# sensor.net
KiCad netlist of a schematic drawn in EAGLE
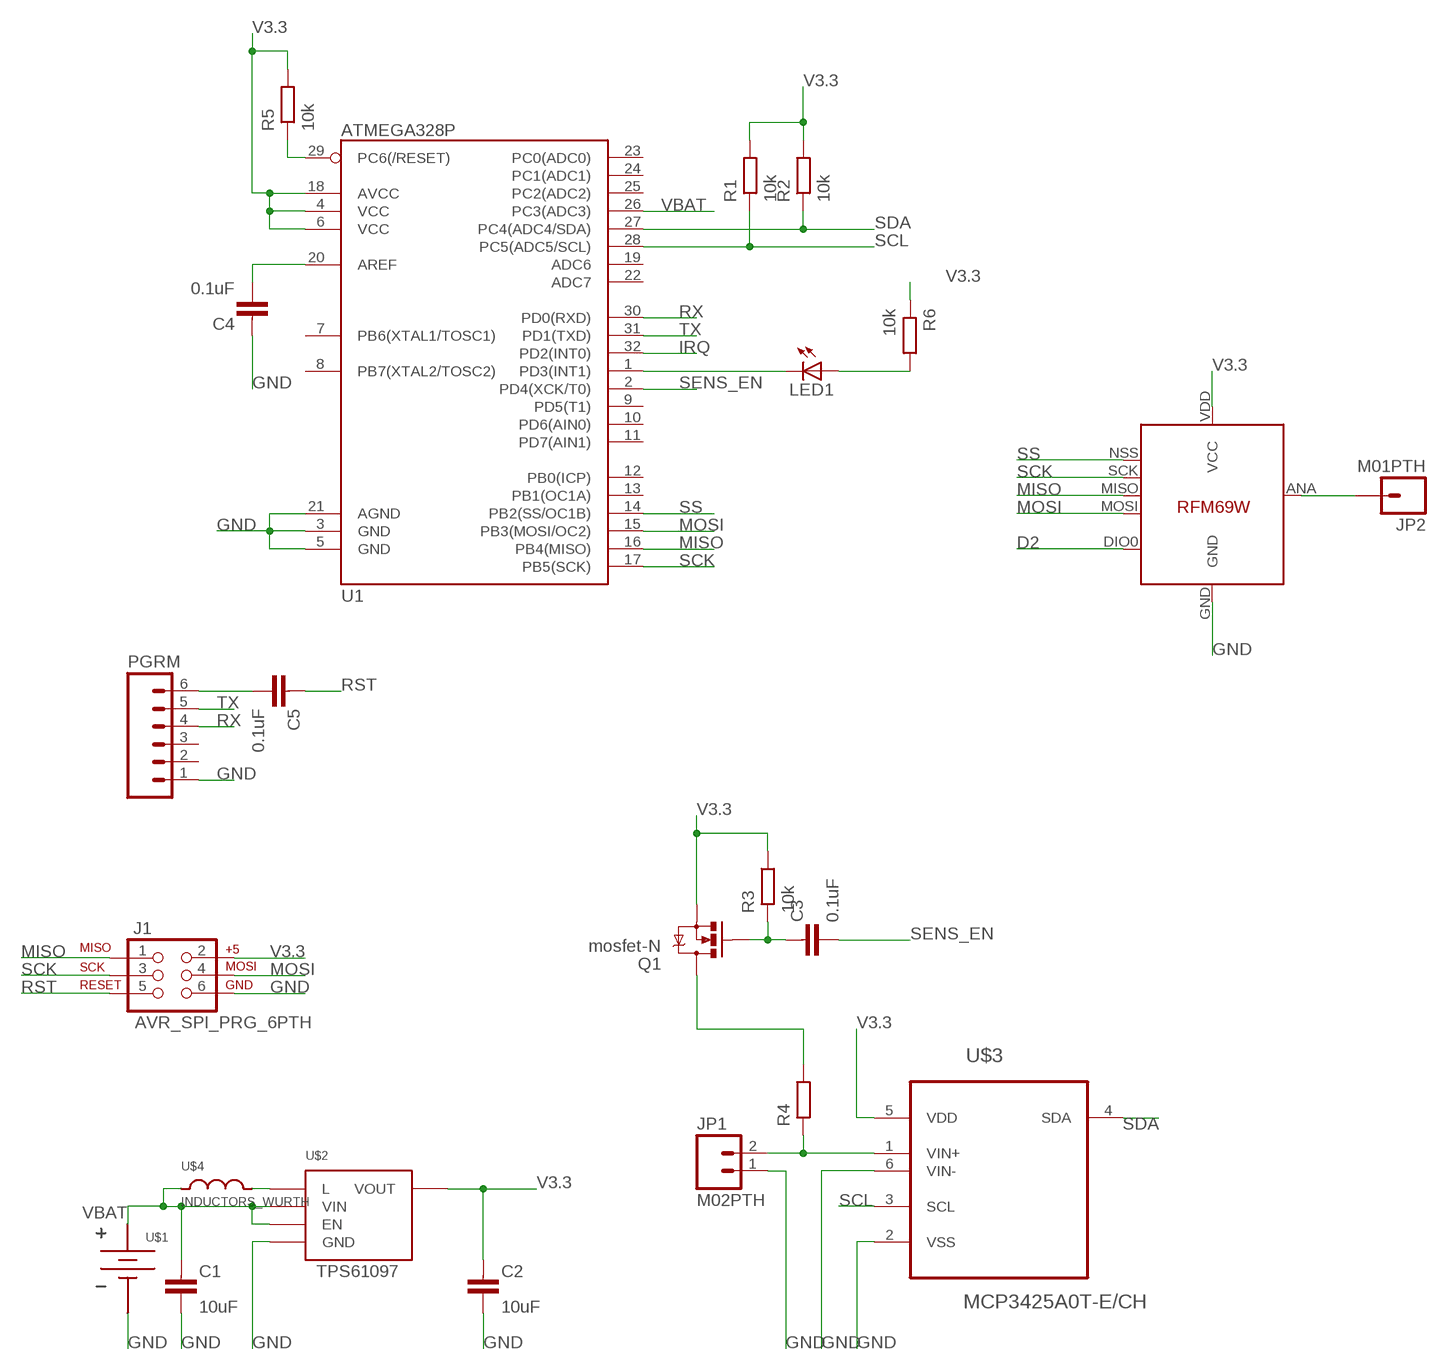
[diagram p0: schematic, sheet 1]

(export (version "E")
  (design (tool "Eeschema 10.0.6"))
  (components
    (comp (ref "C1")
      (value "10uF")
      (footprint "eagle-import:C0805-N")
      (libsource (lib "eagle-import") (part "CAPACITOR0805-N"))
    )
    (comp (ref "C2")
      (value "10uF")
      (footprint "eagle-import:C0805-N")
      (libsource (lib "eagle-import") (part "CAPACITOR0805-N"))
    )
    (comp (ref "C3")
      (value "0.1uF")
      (footprint "eagle-import:C0603-N")
      (libsource (lib "eagle-import") (part "CAPACITOR0603-N"))
    )
    (comp (ref "C4")
      (value "0.1uF")
      (footprint "eagle-import:C0603-N")
      (libsource (lib "eagle-import") (part "CAPACITOR0603-N"))
    )
    (comp (ref "C5")
      (value "0.1uF")
      (footprint "eagle-import:C0603-N")
      (libsource (lib "eagle-import") (part "CAPACITOR0603-N"))
    )
    (comp (ref "J1")
      (value "AVR_SPI_PRG_6PTH")
      (footprint "eagle-import:2X3")
      (libsource (lib "eagle-import") (part "AVR_SPI_PRG_6PTH"))
    )
    (comp (ref "JP1")
      (value "M02PTH")
      (footprint "eagle-import:1X02")
      (libsource (lib "eagle-import") (part "M02PTH"))
    )
    (comp (ref "JP2")
      (value "M01PTH")
      (footprint "eagle-import:1X01")
      (libsource (lib "eagle-import") (part "M01PTH"))
    )
    (comp (ref "LED1")
      (value "LED0603")
      (footprint "eagle-import:LED-0603")
      (libsource (lib "eagle-import") (part "LED0603"))
    )
    (comp (ref "PGRM")
      (value "M06LONGPADS")
      (footprint "eagle-import:1X06_LONGPADS")
      (libsource (lib "eagle-import") (part "M06LONGPADS"))
    )
    (comp (ref "Q1")
      (value "mosfet-N")
      (footprint "eagle-import:SOT23")
      (libsource (lib "eagle-import") (part "MOSFET-NCHANNELBSS123LT1G"))
    )
    (comp (ref "R1")
      (value "10k")
      (footprint "eagle-import:R0603-N")
      (libsource (lib "eagle-import") (part "RESISTOR0603-N"))
    )
    (comp (ref "R2")
      (value "10k")
      (footprint "eagle-import:R0603-N")
      (libsource (lib "eagle-import") (part "RESISTOR0603-N"))
    )
    (comp (ref "R3")
      (value "10k")
      (footprint "eagle-import:R0603-N")
      (libsource (lib "eagle-import") (part "RESISTOR0603-N"))
    )
    (comp (ref "R4")
      (value "RESISTOR0603-N")
      (footprint "eagle-import:R0603-N")
      (libsource (lib "eagle-import") (part "RESISTOR0603-N"))
    )
    (comp (ref "R5")
      (value "10k")
      (footprint "eagle-import:R0603-N")
      (libsource (lib "eagle-import") (part "RESISTOR0603-N"))
    )
    (comp (ref "R6")
      (value "10k")
      (footprint "eagle-import:R0603-N")
      (libsource (lib "eagle-import") (part "RESISTOR0603-N"))
    )
    (comp (ref "U$1")
      (value "KEYSTONEAAHOLDER_2CELL")
      (footprint "eagle-import:KEYSTONEAAHOLDER_2CELL")
      (libsource (lib "eagle-import") (part "KEYSTONEAAHOLDER_2CELL"))
    )
    (comp (ref "U$2")
      (value "TPS61097-33")
      (footprint "eagle-import:SOT23-5")
      (libsource (lib "eagle-import") (part "TPS61097-33"))
    )
    (comp (ref "U$3")
      (value "MCP3425A0T-E/CH")
      (footprint "eagle-import:SOT95P270X145-6N")
      (libsource (lib "eagle-import") (part "MCP3425A0T-E/CH"))
    )
    (comp (ref "U$4")
      (value "INDUCTORS_WURTH")
      (footprint "eagle-import:WURTH_10UH_650MA")
      (libsource (lib "eagle-import") (part "INDUCTORS_WURTH"))
    )
    (comp (ref "U$5")
      (value "RFM69")
      (footprint "eagle-import:RFM69W-MINPADS")
      (libsource (lib "eagle-import") (part "RFM69"))
    )
    (comp (ref "U1")
      (value "ATMEGA328P")
      (footprint "eagle-import:TQFP32-08")
      (libsource (lib "eagle-import") (part "ATMEGA328_SMT"))
    )
  )
  (nets
    (net (code "1") (name "/D2") (class "Default")
      (node (ref "U$5") (pin "DIO0") (pinfunction "DIO0_DIO0") (pintype "open_collector"))
    )
    (net (code "2") (name "/GND") (class "Default")
      (node (ref "C1") (pin "2") (pinfunction "2_2") (pintype "passive"))
      (node (ref "C2") (pin "2") (pinfunction "2_2") (pintype "passive"))
      (node (ref "C4") (pin "1") (pinfunction "1_1") (pintype "passive"))
      (node (ref "J1") (pin "6") (pinfunction "6_6") (pintype "passive"))
      (node (ref "JP1") (pin "1") (pinfunction "1_1") (pintype "passive"))
      (node (ref "PGRM") (pin "1") (pinfunction "1_1") (pintype "passive"))
      (node (ref "U$1") (pin "P$2") (pinfunction "GND_P$2") (pintype "bidirectional"))
      (node (ref "U$2") (pin "P$2") (pinfunction "GND_P$2") (pintype "power_in"))
      (node (ref "U$3") (pin "2") (pinfunction "VSS_2") (pintype "passive"))
      (node (ref "U$3") (pin "6") (pinfunction "VIN-_6") (pintype "input"))
      (node (ref "U$5") (pin "GND") (pinfunction "GND_GND") (pintype "power_in"))
      (node (ref "U1") (pin "21") (pinfunction "AGND_21") (pintype "bidirectional"))
      (node (ref "U1") (pin "3") (pinfunction "GND_3") (pintype "bidirectional"))
      (node (ref "U1") (pin "5") (pinfunction "GND_5") (pintype "bidirectional"))
    )
    (net (code "3") (name "/IRQ") (class "Default")
      (node (ref "U1") (pin "32") (pinfunction "PD2(INT0)_32") (pintype "bidirectional"))
    )
    (net (code "4") (name "/MISO") (class "Default")
      (node (ref "J1") (pin "1") (pinfunction "1_1") (pintype "passive"))
      (node (ref "U$5") (pin "MISO") (pinfunction "MISO_MISO") (pintype "input"))
      (node (ref "U1") (pin "16") (pinfunction "PB4(MISO)_16") (pintype "bidirectional"))
    )
    (net (code "5") (name "/MOSI") (class "Default")
      (node (ref "J1") (pin "4") (pinfunction "4_4") (pintype "passive"))
      (node (ref "U$5") (pin "MOSI") (pinfunction "MOSI_MOSI") (pintype "output"))
      (node (ref "U1") (pin "15") (pinfunction "PB3(MOSI/OC2)_15") (pintype "bidirectional"))
    )
    (net (code "6") (name "/RST") (class "Default")
      (node (ref "C5") (pin "1") (pinfunction "1_1") (pintype "passive"))
      (node (ref "J1") (pin "5") (pinfunction "5_5") (pintype "passive"))
      (node (ref "R5") (pin "1") (pinfunction "P$1_1") (pintype "passive"))
      (node (ref "U1") (pin "29") (pinfunction "PC6(/RESET)_29") (pintype "bidirectional"))
    )
    (net (code "7") (name "/RX") (class "Default")
      (node (ref "PGRM") (pin "4") (pinfunction "4_4") (pintype "passive"))
      (node (ref "U1") (pin "30") (pinfunction "PD0(RXD)_30") (pintype "bidirectional"))
    )
    (net (code "8") (name "/SCK") (class "Default")
      (node (ref "J1") (pin "3") (pinfunction "3_3") (pintype "passive"))
      (node (ref "U$5") (pin "SCK") (pinfunction "SCK_SCK") (pintype "input"))
      (node (ref "U1") (pin "17") (pinfunction "PB5(SCK)_17") (pintype "bidirectional"))
    )
    (net (code "9") (name "/SCL") (class "Default")
      (node (ref "R1") (pin "1") (pinfunction "P$1_1") (pintype "passive"))
      (node (ref "U$3") (pin "3") (pinfunction "SCL_3") (pintype "input"))
      (node (ref "U1") (pin "28") (pinfunction "PC5(ADC5/SCL)_28") (pintype "bidirectional"))
    )
    (net (code "10") (name "/SDA") (class "Default")
      (node (ref "R2") (pin "1") (pinfunction "P$1_1") (pintype "passive"))
      (node (ref "U$3") (pin "4") (pinfunction "SDA_4") (pintype "bidirectional"))
      (node (ref "U1") (pin "27") (pinfunction "PC4(ADC4/SDA)_27") (pintype "bidirectional"))
    )
    (net (code "11") (name "/SENS_EN") (class "Default")
      (node (ref "C3") (pin "2") (pinfunction "2_2") (pintype "passive"))
      (node (ref "U1") (pin "2") (pinfunction "PD4(XCK/T0)_2") (pintype "bidirectional"))
    )
    (net (code "12") (name "/SS") (class "Default")
      (node (ref "U$5") (pin "NSS") (pinfunction "SEL_NSS") (pintype "input"))
      (node (ref "U1") (pin "14") (pinfunction "PB2(SS/OC1B)_14") (pintype "bidirectional"))
    )
    (net (code "13") (name "/TX") (class "Default")
      (node (ref "PGRM") (pin "5") (pinfunction "5_5") (pintype "passive"))
      (node (ref "U1") (pin "31") (pinfunction "PD1(TXD)_31") (pintype "bidirectional"))
    )
    (net (code "14") (name "/V3.3") (class "Default")
      (node (ref "C2") (pin "1") (pinfunction "1_1") (pintype "passive"))
      (node (ref "J1") (pin "2") (pinfunction "2_2") (pintype "passive"))
      (node (ref "Q1") (pin "2") (pinfunction "S_2") (pintype "passive"))
      (node (ref "R1") (pin "2") (pinfunction "P$2_2") (pintype "passive"))
      (node (ref "R2") (pin "2") (pinfunction "P$2_2") (pintype "passive"))
      (node (ref "R3") (pin "2") (pinfunction "P$2_2") (pintype "passive"))
      (node (ref "R5") (pin "2") (pinfunction "P$2_2") (pintype "passive"))
      (node (ref "R6") (pin "1") (pinfunction "P$1_1") (pintype "passive"))
      (node (ref "U$2") (pin "P$4") (pinfunction "VOUT_P$4") (pintype "power_in"))
      (node (ref "U$3") (pin "5") (pinfunction "VDD_5") (pintype "power_in"))
      (node (ref "U$5") (pin "VDD") (pinfunction "VCC_VDD") (pintype "power_in"))
      (node (ref "U1") (pin "18") (pinfunction "AVCC_18") (pintype "bidirectional"))
      (node (ref "U1") (pin "4") (pinfunction "VCC_4") (pintype "bidirectional"))
      (node (ref "U1") (pin "6") (pinfunction "VCC_6") (pintype "bidirectional"))
    )
    (net (code "15") (name "/VBAT") (class "Default")
      (node (ref "C1") (pin "1") (pinfunction "1_1") (pintype "passive"))
      (node (ref "U$1") (pin "P$1") (pinfunction "VBAT_P$1") (pintype "bidirectional"))
      (node (ref "U$2") (pin "P$1") (pinfunction "VIN_P$1") (pintype "power_in"))
      (node (ref "U$2") (pin "P$3") (pinfunction "EN_P$3") (pintype "bidirectional"))
      (node (ref "U$4") (pin "P$2") (pinfunction "P$2_P$2") (pintype "passive"))
      (node (ref "U1") (pin "26") (pinfunction "PC3(ADC3)_26") (pintype "bidirectional"))
    )
    (net (code "16") (name "Net-(C5-Pad2)") (class "Default")
      (node (ref "C5") (pin "2") (pinfunction "2_2") (pintype "passive"))
      (node (ref "PGRM") (pin "6") (pinfunction "6_6") (pintype "passive"))
    )
    (net (code "17") (name "Net-(Q1-D)") (class "Default")
      (node (ref "Q1") (pin "3") (pinfunction "D_3") (pintype "passive"))
      (node (ref "R4") (pin "2") (pinfunction "P$2_2") (pintype "passive"))
    )
    (net (code "18") (name "Net-(Q1-G)") (class "Default")
      (node (ref "C3") (pin "1") (pinfunction "1_1") (pintype "passive"))
      (node (ref "Q1") (pin "1") (pinfunction "G_1") (pintype "passive"))
      (node (ref "R3") (pin "1") (pinfunction "P$1_1") (pintype "passive"))
    )
    (net (code "19") (name "Net-(R4-P$1)") (class "Default")
      (node (ref "JP1") (pin "2") (pinfunction "2_2") (pintype "passive"))
      (node (ref "R4") (pin "1") (pinfunction "P$1_1") (pintype "passive"))
      (node (ref "U$3") (pin "1") (pinfunction "VIN+_1") (pintype "input"))
    )
    (net (code "20") (name "Net-(R6-P$2)") (class "Default")
      (node (ref "LED1") (pin "A") (pinfunction "A_A") (pintype "passive"))
      (node (ref "R6") (pin "2") (pinfunction "P$2_2") (pintype "passive"))
    )
    (net (code "21") (name "Net-(U$2-L)") (class "Default")
      (node (ref "U$2") (pin "P$5") (pinfunction "L_P$5") (pintype "bidirectional"))
      (node (ref "U$4") (pin "P$1") (pinfunction "P$1_P$1") (pintype "passive"))
    )
    (net (code "22") (name "Net-(U$5-ANT)") (class "Default")
      (node (ref "JP2") (pin "1") (pinfunction "1_1") (pintype "passive"))
      (node (ref "U$5") (pin "ANA") (pinfunction "ANT_ANA") (pintype "passive"))
    )
    (net (code "23") (name "Net-(U1-AREF)") (class "Default")
      (node (ref "C4") (pin "2") (pinfunction "2_2") (pintype "passive"))
      (node (ref "U1") (pin "20") (pinfunction "AREF_20") (pintype "bidirectional"))
    )
    (net (code "24") (name "Net-(U1-PD3(INT1))") (class "Default")
      (node (ref "LED1") (pin "C") (pinfunction "C_C") (pintype "passive"))
      (node (ref "U1") (pin "1") (pinfunction "PD3(INT1)_1") (pintype "bidirectional"))
    )
    (net (code "25") (name "unconnected-(PGRM-Pad2)") (class "Default")
      (node (ref "PGRM") (pin "2") (pinfunction "2_2") (pintype "passive"))
    )
    (net (code "26") (name "unconnected-(PGRM-Pad3)") (class "Default")
      (node (ref "PGRM") (pin "3") (pinfunction "3_3") (pintype "passive"))
    )
    (net (code "27") (name "unconnected-(U1-ADC6-Pad19)") (class "Default")
      (node (ref "U1") (pin "19") (pinfunction "ADC6_19") (pintype "bidirectional"))
    )
    (net (code "28") (name "unconnected-(U1-ADC7-Pad22)") (class "Default")
      (node (ref "U1") (pin "22") (pinfunction "ADC7_22") (pintype "bidirectional"))
    )
    (net (code "29") (name "unconnected-(U1-PB0(ICP)-Pad12)") (class "Default")
      (node (ref "U1") (pin "12") (pinfunction "PB0(ICP)_12") (pintype "bidirectional"))
    )
    (net (code "30") (name "unconnected-(U1-PB1(OC1A)-Pad13)") (class "Default")
      (node (ref "U1") (pin "13") (pinfunction "PB1(OC1A)_13") (pintype "bidirectional"))
    )
    (net (code "31") (name "unconnected-(U1-PB6(XTAL1{slash}TOSC1)-Pad7)") (class "Default")
      (node (ref "U1") (pin "7") (pinfunction "PB6(XTAL1/TOSC1)_7") (pintype "bidirectional"))
    )
    (net (code "32") (name "unconnected-(U1-PB7(XTAL2{slash}TOSC2)-Pad8)") (class "Default")
      (node (ref "U1") (pin "8") (pinfunction "PB7(XTAL2/TOSC2)_8") (pintype "bidirectional"))
    )
    (net (code "33") (name "unconnected-(U1-PC0(ADC0)-Pad23)") (class "Default")
      (node (ref "U1") (pin "23") (pinfunction "PC0(ADC0)_23") (pintype "bidirectional"))
    )
    (net (code "34") (name "unconnected-(U1-PC1(ADC1)-Pad24)") (class "Default")
      (node (ref "U1") (pin "24") (pinfunction "PC1(ADC1)_24") (pintype "bidirectional"))
    )
    (net (code "35") (name "unconnected-(U1-PC2(ADC2)-Pad25)") (class "Default")
      (node (ref "U1") (pin "25") (pinfunction "PC2(ADC2)_25") (pintype "bidirectional"))
    )
    (net (code "36") (name "unconnected-(U1-PD5(T1)-Pad9)") (class "Default")
      (node (ref "U1") (pin "9") (pinfunction "PD5(T1)_9") (pintype "bidirectional"))
    )
    (net (code "37") (name "unconnected-(U1-PD6(AIN0)-Pad10)") (class "Default")
      (node (ref "U1") (pin "10") (pinfunction "PD6(AIN0)_10") (pintype "bidirectional"))
    )
    (net (code "38") (name "unconnected-(U1-PD7(AIN1)-Pad11)") (class "Default")
      (node (ref "U1") (pin "11") (pinfunction "PD7(AIN1)_11") (pintype "bidirectional"))
    )
  )
)
